# Digital_IO_HS.net
KiCad netlist of a schematic drawn in Altium Designer
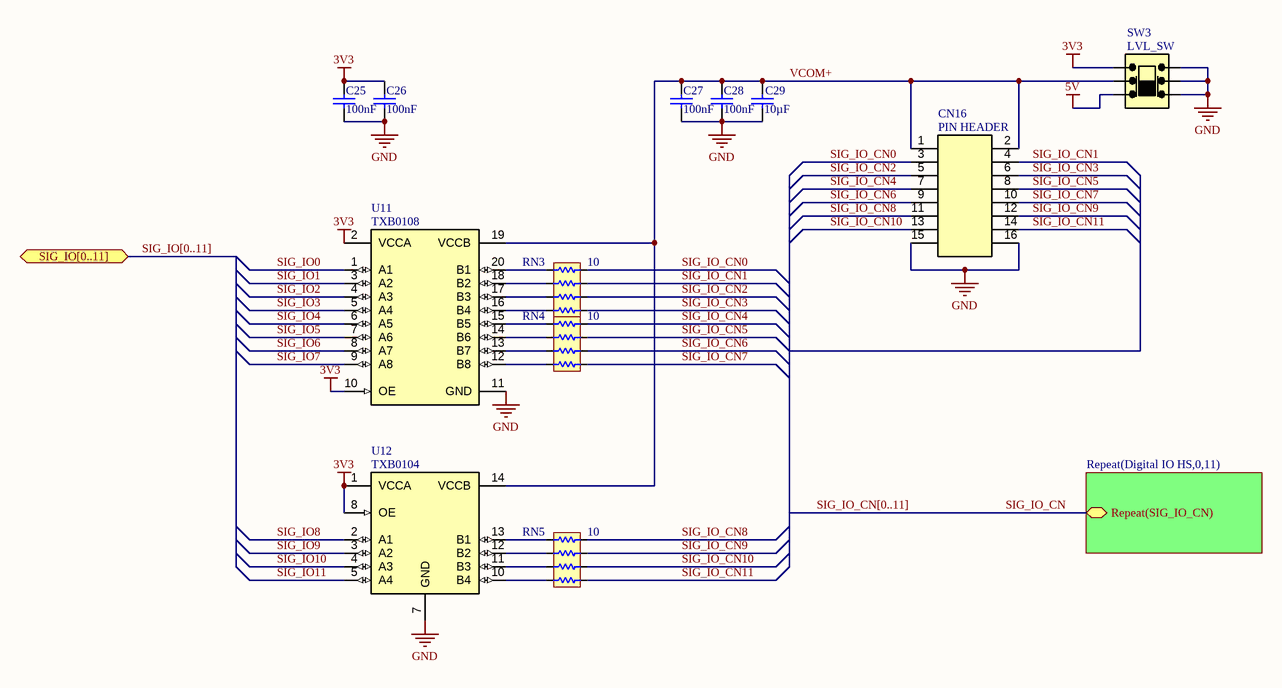
[diagram p0: Digital IO HS.SchDoc]

(export (version "E")
  (design (tool "Eeschema 10.0.6"))
  (components
    (comp (ref "C25")
      (value "100nF")
      (footprint "CAP_CHIP_0603")
      (description "0603 Multilayer Ceramic Capacitors MLCC")
      (fields (field (name "TOLERANCE") "10%") (field (name "PARTNUMBER") "CC0603KRX7R9BB104"))
      (libsource (lib "Sainsbury Wellcome Centre") (part "Cap"))
    )
    (comp (ref "C26")
      (value "100nF")
      (footprint "CAP_CHIP_0603")
      (description "0603 Multilayer Ceramic Capacitors MLCC")
      (fields (field (name "TOLERANCE") "10%") (field (name "PARTNUMBER") "CC0603KRX7R9BB104"))
      (libsource (lib "Sainsbury Wellcome Centre") (part "Cap"))
    )
    (comp (ref "C27")
      (value "100nF")
      (footprint "CAP_CHIP_0603")
      (description "0603 Multilayer Ceramic Capacitors MLCC")
      (fields (field (name "TOLERANCE") "10%") (field (name "PARTNUMBER") "CC0603KRX7R9BB104"))
      (libsource (lib "Sainsbury Wellcome Centre") (part "Cap"))
    )
    (comp (ref "C28")
      (value "100nF")
      (footprint "CAP_CHIP_0603")
      (description "0603 Multilayer Ceramic Capacitors MLCC")
      (fields (field (name "TOLERANCE") "10%") (field (name "PARTNUMBER") "CC0603KRX7R9BB104"))
      (libsource (lib "Sainsbury Wellcome Centre") (part "Cap"))
    )
    (comp (ref "C29")
      (value "10µF")
      (footprint "CAP_CHIP_0603")
      (fields
        (field (name "PARTNUMBER") "GRM188R6YA106MA73D")
        (field (name "TOLERANCE") "20%")
        (field (name "Comment") "C0603-10uF-35V")
      )
      (libsource (lib "Sainsbury Wellcome Centre") (part "Cap"))
    )
    (comp (ref "CN16")
      (value "PIN HEADER")
      (footprint "PIN_2.54_2X8P")
      (fields (field (name "PARTNUMBER") "PZ254V-12-16P"))
      (libsource (lib "Sainsbury Wellcome Centre") (part "Header_2X8P"))
    )
    (comp (ref "RN3")
      (value "10")
      (footprint "RES_ARRAY_0603")
      (fields
        (field (name "TOLERANCE") "5%")
        (field (name "PARTNUMBER") "4D03WGJ0100T5E")
        (field (name "Comment") "RN0603-10R")
      )
      (libsource (lib "Sainsbury Wellcome Centre") (part "Res Array 4P"))
    )
    (comp (ref "RN4")
      (value "10")
      (footprint "RES_ARRAY_0603")
      (fields
        (field (name "TOLERANCE") "5%")
        (field (name "PARTNUMBER") "4D03WGJ0100T5E")
        (field (name "Comment") "RN0603-10R")
      )
      (libsource (lib "Sainsbury Wellcome Centre") (part "Res Array 4P"))
    )
    (comp (ref "RN5")
      (value "10")
      (footprint "RES_ARRAY_0603")
      (fields
        (field (name "TOLERANCE") "5%")
        (field (name "PARTNUMBER") "4D03WGJ0100T5E")
        (field (name "Comment") "RN0603-10R")
      )
      (libsource (lib "Sainsbury Wellcome Centre") (part "Res Array 4P"))
    )
    (comp (ref "SW3")
      (value "LVL_SW")
      (footprint "SW_SLIDE_OS202013MT8")
      (description "Switch Slide ON ON DPDT Top Slide 0.3A 30VDC 10000Cycles PC Pins Thru-Hole Bulk")
      (fields (field (name "PARTNUMBER") "OS202013MT8QN1"))
      (libsource (lib "Sainsbury Wellcome Centre") (part "SLIDE_DPDT"))
    )
    (comp (ref "U11")
      (value "TXB0108")
      (footprint "TSSOP20_6.5X4.4_0.65E")
      (fields (field (name "PARTNUMBER") "TXB0108PWR"))
      (libsource (lib "Sainsbury Wellcome Centre") (part "TXB0108"))
    )
    (comp (ref "U12")
      (value "TXB0104")
      (footprint "TSSOP14_5X4.4_0.65E")
      (fields (field (name "PARTNUMBER") "TXB0104PWR"))
      (libsource (lib "Sainsbury Wellcome Centre") (part "TXB0104PWR"))
    )
  )
  (nets
    (net (code "1") (name "/SIG_IO0") (class "Default")
      (node (ref "U11") (pin "1") (pinfunction "A1_1") (pintype "bidirectional"))
    )
    (net (code "2") (name "/SIG_IO1") (class "Default")
      (node (ref "U11") (pin "3") (pinfunction "A2_3") (pintype "bidirectional"))
    )
    (net (code "3") (name "/SIG_IO2") (class "Default")
      (node (ref "U11") (pin "4") (pinfunction "A3_4") (pintype "bidirectional"))
    )
    (net (code "4") (name "/SIG_IO3") (class "Default")
      (node (ref "U11") (pin "5") (pinfunction "A4_5") (pintype "bidirectional"))
    )
    (net (code "5") (name "/SIG_IO4") (class "Default")
      (node (ref "U11") (pin "6") (pinfunction "A5_6") (pintype "bidirectional"))
    )
    (net (code "6") (name "/SIG_IO5") (class "Default")
      (node (ref "U11") (pin "7") (pinfunction "A6_7") (pintype "bidirectional"))
    )
    (net (code "7") (name "/SIG_IO6") (class "Default")
      (node (ref "U11") (pin "8") (pinfunction "A7_8") (pintype "bidirectional"))
    )
    (net (code "8") (name "/SIG_IO7") (class "Default")
      (node (ref "U11") (pin "9") (pinfunction "A8_9") (pintype "bidirectional"))
    )
    (net (code "9") (name "/SIG_IO8") (class "Default")
      (node (ref "U12") (pin "2") (pinfunction "A1_2") (pintype "bidirectional"))
    )
    (net (code "10") (name "/SIG_IO9") (class "Default")
      (node (ref "U12") (pin "3") (pinfunction "A2_3") (pintype "bidirectional"))
    )
    (net (code "11") (name "/SIG_IO10") (class "Default")
      (node (ref "U12") (pin "4") (pinfunction "A3_4") (pintype "bidirectional"))
    )
    (net (code "12") (name "/SIG_IO11") (class "Default")
      (node (ref "U12") (pin "5") (pinfunction "A4_5") (pintype "bidirectional"))
    )
    (net (code "15") (name "/SIG_IO_CN0") (class "Default")
      (node (ref "CN16") (pin "3") (pinfunction "3_3") (pintype "passive"))
      (node (ref "RN3") (pin "8") (pinfunction "8_8") (pintype "passive"))
    )
    (net (code "16") (name "/SIG_IO_CN1") (class "Default")
      (node (ref "CN16") (pin "4") (pinfunction "4_4") (pintype "passive"))
      (node (ref "RN3") (pin "7") (pinfunction "7_7") (pintype "passive"))
    )
    (net (code "17") (name "/SIG_IO_CN2") (class "Default")
      (node (ref "CN16") (pin "5") (pinfunction "5_5") (pintype "passive"))
      (node (ref "RN3") (pin "6") (pinfunction "6_6") (pintype "passive"))
    )
    (net (code "18") (name "/SIG_IO_CN3") (class "Default")
      (node (ref "CN16") (pin "6") (pinfunction "6_6") (pintype "passive"))
      (node (ref "RN3") (pin "5") (pinfunction "5_5") (pintype "passive"))
    )
    (net (code "19") (name "/SIG_IO_CN4") (class "Default")
      (node (ref "CN16") (pin "7") (pinfunction "7_7") (pintype "passive"))
      (node (ref "RN4") (pin "8") (pinfunction "8_8") (pintype "passive"))
    )
    (net (code "20") (name "/SIG_IO_CN5") (class "Default")
      (node (ref "CN16") (pin "8") (pinfunction "8_8") (pintype "passive"))
      (node (ref "RN4") (pin "7") (pinfunction "7_7") (pintype "passive"))
    )
    (net (code "21") (name "/SIG_IO_CN6") (class "Default")
      (node (ref "CN16") (pin "9") (pinfunction "9_9") (pintype "passive"))
      (node (ref "RN4") (pin "6") (pinfunction "6_6") (pintype "passive"))
    )
    (net (code "22") (name "/SIG_IO_CN7") (class "Default")
      (node (ref "CN16") (pin "10") (pinfunction "10_10") (pintype "passive"))
      (node (ref "RN4") (pin "5") (pinfunction "5_5") (pintype "passive"))
    )
    (net (code "23") (name "/SIG_IO_CN8") (class "Default")
      (node (ref "CN16") (pin "11") (pinfunction "11_11") (pintype "passive"))
      (node (ref "RN5") (pin "8") (pinfunction "8_8") (pintype "passive"))
    )
    (net (code "24") (name "/SIG_IO_CN9") (class "Default")
      (node (ref "CN16") (pin "12") (pinfunction "12_12") (pintype "passive"))
      (node (ref "RN5") (pin "7") (pinfunction "7_7") (pintype "passive"))
    )
    (net (code "25") (name "/SIG_IO_CN10") (class "Default")
      (node (ref "CN16") (pin "13") (pinfunction "13_13") (pintype "passive"))
      (node (ref "RN5") (pin "6") (pinfunction "6_6") (pintype "passive"))
    )
    (net (code "26") (name "/SIG_IO_CN11") (class "Default")
      (node (ref "CN16") (pin "14") (pinfunction "14_14") (pintype "passive"))
      (node (ref "RN5") (pin "5") (pinfunction "5_5") (pintype "passive"))
    )
    (net (code "28") (name "/VCOM+") (class "Default")
      (node (ref "C27") (pin "2") (pinfunction "2_2") (pintype "passive"))
      (node (ref "C28") (pin "2") (pinfunction "2_2") (pintype "passive"))
      (node (ref "C29") (pin "2") (pinfunction "2_2") (pintype "passive"))
      (node (ref "CN16") (pin "1") (pinfunction "1_1") (pintype "passive"))
      (node (ref "CN16") (pin "2") (pinfunction "2_2") (pintype "passive"))
      (node (ref "SW3") (pin "2") (pinfunction "COMA_2") (pintype "passive"))
      (node (ref "U11") (pin "19") (pinfunction "VCCB_19") (pintype "power_in"))
      (node (ref "U12") (pin "14") (pinfunction "VCCB_14") (pintype "power_in"))
    )
    (net (code "29") (name "3V3") (class "Default")
      (node (ref "C25") (pin "2") (pinfunction "2_2") (pintype "passive"))
      (node (ref "C26") (pin "2") (pinfunction "2_2") (pintype "passive"))
      (node (ref "SW3") (pin "3") (pinfunction "NOA_3") (pintype "passive"))
      (node (ref "U11") (pin "10") (pinfunction "OE_10") (pintype "input"))
      (node (ref "U11") (pin "2") (pinfunction "VCCA_2") (pintype "power_in"))
      (node (ref "U12") (pin "1") (pinfunction "VCCA_1") (pintype "power_in"))
      (node (ref "U12") (pin "8") (pinfunction "OE_8") (pintype "input"))
    )
    (net (code "30") (name "5V") (class "Default")
      (node (ref "SW3") (pin "1") (pinfunction "NCA_1") (pintype "passive"))
    )
    (net (code "31") (name "GND") (class "Default")
      (node (ref "C25") (pin "1") (pinfunction "1_1") (pintype "passive"))
      (node (ref "C26") (pin "1") (pinfunction "1_1") (pintype "passive"))
      (node (ref "C27") (pin "1") (pinfunction "1_1") (pintype "passive"))
      (node (ref "C28") (pin "1") (pinfunction "1_1") (pintype "passive"))
      (node (ref "C29") (pin "1") (pinfunction "1_1") (pintype "passive"))
      (node (ref "CN16") (pin "15") (pinfunction "15_15") (pintype "passive"))
      (node (ref "CN16") (pin "16") (pinfunction "16_16") (pintype "passive"))
      (node (ref "SW3") (pin "4") (pinfunction "NCB_4") (pintype "passive"))
      (node (ref "SW3") (pin "5") (pinfunction "COMB_5") (pintype "passive"))
      (node (ref "SW3") (pin "6") (pinfunction "NOB_6") (pintype "passive"))
      (node (ref "U11") (pin "11") (pinfunction "GND_11") (pintype "power_in"))
      (node (ref "U12") (pin "7") (pinfunction "GND_7") (pintype "power_in"))
    )
    (net (code "32") (name "Net-(U11-B1)") (class "Default")
      (node (ref "RN3") (pin "1") (pinfunction "1_1") (pintype "passive"))
      (node (ref "U11") (pin "20") (pinfunction "B1_20") (pintype "bidirectional"))
    )
    (net (code "33") (name "Net-(U11-B2)") (class "Default")
      (node (ref "RN3") (pin "2") (pinfunction "2_2") (pintype "passive"))
      (node (ref "U11") (pin "18") (pinfunction "B2_18") (pintype "bidirectional"))
    )
    (net (code "34") (name "Net-(U11-B3)") (class "Default")
      (node (ref "RN3") (pin "3") (pinfunction "3_3") (pintype "passive"))
      (node (ref "U11") (pin "17") (pinfunction "B3_17") (pintype "bidirectional"))
    )
    (net (code "35") (name "Net-(U11-B4)") (class "Default")
      (node (ref "RN3") (pin "4") (pinfunction "4_4") (pintype "passive"))
      (node (ref "U11") (pin "16") (pinfunction "B4_16") (pintype "bidirectional"))
    )
    (net (code "36") (name "Net-(U11-B5)") (class "Default")
      (node (ref "RN4") (pin "1") (pinfunction "1_1") (pintype "passive"))
      (node (ref "U11") (pin "15") (pinfunction "B5_15") (pintype "bidirectional"))
    )
    (net (code "37") (name "Net-(U11-B6)") (class "Default")
      (node (ref "RN4") (pin "2") (pinfunction "2_2") (pintype "passive"))
      (node (ref "U11") (pin "14") (pinfunction "B6_14") (pintype "bidirectional"))
    )
    (net (code "38") (name "Net-(U11-B7)") (class "Default")
      (node (ref "RN4") (pin "3") (pinfunction "3_3") (pintype "passive"))
      (node (ref "U11") (pin "13") (pinfunction "B7_13") (pintype "bidirectional"))
    )
    (net (code "39") (name "Net-(U11-B8)") (class "Default")
      (node (ref "RN4") (pin "4") (pinfunction "4_4") (pintype "passive"))
      (node (ref "U11") (pin "12") (pinfunction "B8_12") (pintype "bidirectional"))
    )
    (net (code "40") (name "Net-(U12-B1)") (class "Default")
      (node (ref "RN5") (pin "1") (pinfunction "1_1") (pintype "passive"))
      (node (ref "U12") (pin "13") (pinfunction "B1_13") (pintype "bidirectional"))
    )
    (net (code "41") (name "Net-(U12-B2)") (class "Default")
      (node (ref "RN5") (pin "2") (pinfunction "2_2") (pintype "passive"))
      (node (ref "U12") (pin "12") (pinfunction "B2_12") (pintype "bidirectional"))
    )
    (net (code "42") (name "Net-(U12-B3)") (class "Default")
      (node (ref "RN5") (pin "3") (pinfunction "3_3") (pintype "passive"))
      (node (ref "U12") (pin "11") (pinfunction "B3_11") (pintype "bidirectional"))
    )
    (net (code "43") (name "Net-(U12-B4)") (class "Default")
      (node (ref "RN5") (pin "4") (pinfunction "4_4") (pintype "passive"))
      (node (ref "U12") (pin "10") (pinfunction "B4_10") (pintype "bidirectional"))
    )
  )
)
